# IOBoard.net
KiCad netlist of a schematic drawn in EAGLE
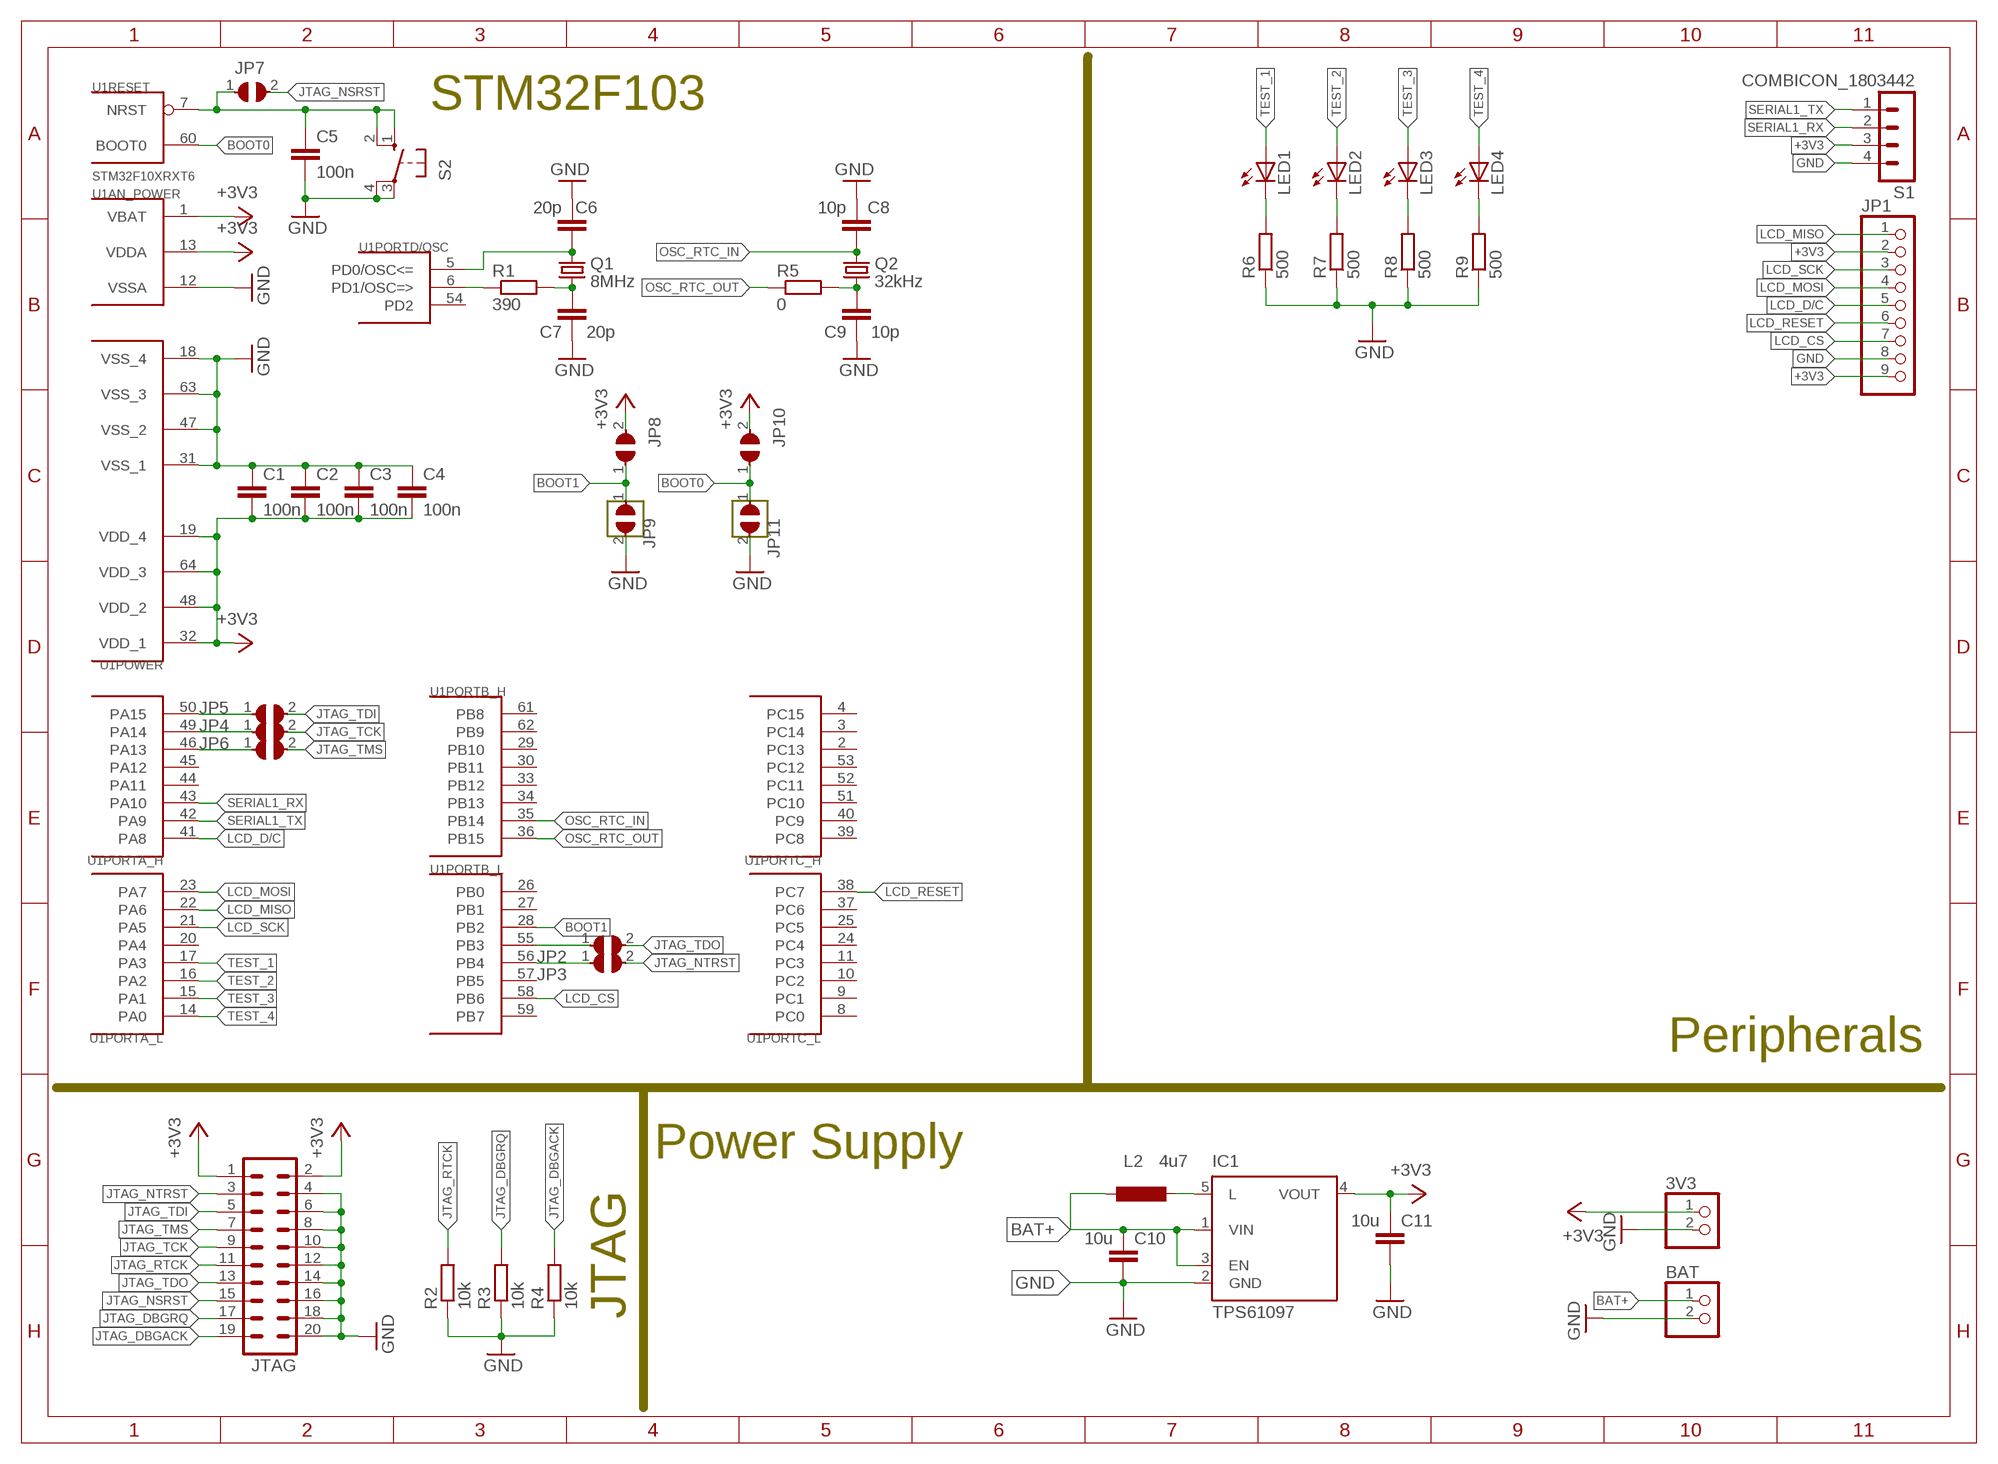
[diagram p0: schematic, sheet 1]

(export (version "E")
  (design (tool "Eeschema 10.0.6"))
  (components
    (comp (ref "3V3")
      (value "PINHD-1X2")
      (footprint "eagle-import:1X02")
      (libsource (lib "eagle-import") (part "PINHD-1X2"))
    )
    (comp (ref "BAT")
      (value "PINHD-1X2")
      (footprint "eagle-import:1X02")
      (libsource (lib "eagle-import") (part "PINHD-1X2"))
    )
    (comp (ref "C1")
      (value "100n")
      (footprint "eagle-import:C0805")
      (libsource (lib "eagle-import") (part "C-EUC0805"))
    )
    (comp (ref "C2")
      (value "100n")
      (footprint "eagle-import:C0805")
      (libsource (lib "eagle-import") (part "C-EUC0805"))
    )
    (comp (ref "C3")
      (value "100n")
      (footprint "eagle-import:C0805")
      (libsource (lib "eagle-import") (part "C-EUC0805"))
    )
    (comp (ref "C4")
      (value "100n")
      (footprint "eagle-import:C0805")
      (libsource (lib "eagle-import") (part "C-EUC0805"))
    )
    (comp (ref "C5")
      (value "100n")
      (footprint "eagle-import:C0805")
      (libsource (lib "eagle-import") (part "C-EUC0805"))
    )
    (comp (ref "C6")
      (value "20p")
      (footprint "eagle-import:C0805")
      (libsource (lib "eagle-import") (part "C-EUC0805"))
    )
    (comp (ref "C7")
      (value "20p")
      (footprint "eagle-import:C0805")
      (libsource (lib "eagle-import") (part "C-EUC0805"))
    )
    (comp (ref "C8")
      (value "10p")
      (footprint "eagle-import:C0805")
      (libsource (lib "eagle-import") (part "C-EUC0805"))
    )
    (comp (ref "C9")
      (value "10p")
      (footprint "eagle-import:C0805")
      (libsource (lib "eagle-import") (part "C-EUC0805"))
    )
    (comp (ref "C10")
      (value "10u")
      (footprint "eagle-import:C0805")
      (libsource (lib "eagle-import") (part "C-EUC0805"))
    )
    (comp (ref "C11")
      (value "10u")
      (footprint "eagle-import:C0805")
      (libsource (lib "eagle-import") (part "C-EUC0805"))
    )
    (comp (ref "IC1")
      (value "TPS61097")
      (footprint "eagle-import:SOT23-DBV")
      (libsource (lib "eagle-import") (part "TPS61097"))
    )
    (comp (ref "JP1")
      (value "PINHD-1X9")
      (footprint "eagle-import:1X09")
      (libsource (lib "eagle-import") (part "PINHD-1X9"))
    )
    (comp (ref "JP2")
      (value "JUMPER_SMALL")
      (footprint "eagle-import:JUMPER")
      (libsource (lib "eagle-import") (part "JUMPER_SMALL"))
    )
    (comp (ref "JP3")
      (value "JUMPER_SMALL")
      (footprint "eagle-import:JUMPER")
      (libsource (lib "eagle-import") (part "JUMPER_SMALL"))
    )
    (comp (ref "JP4")
      (value "JUMPER_SMALL")
      (footprint "eagle-import:JUMPER")
      (libsource (lib "eagle-import") (part "JUMPER_SMALL"))
    )
    (comp (ref "JP5")
      (value "JUMPER_SMALL")
      (footprint "eagle-import:JUMPER")
      (libsource (lib "eagle-import") (part "JUMPER_SMALL"))
    )
    (comp (ref "JP6")
      (value "JUMPER_SMALL")
      (footprint "eagle-import:JUMPER")
      (libsource (lib "eagle-import") (part "JUMPER_SMALL"))
    )
    (comp (ref "JP7")
      (value "JUMPER_SMALL")
      (footprint "eagle-import:JUMPER")
      (libsource (lib "eagle-import") (part "JUMPER_SMALL"))
    )
    (comp (ref "JP8")
      (value "JUMPER_SMALL")
      (footprint "eagle-import:JUMPER")
      (libsource (lib "eagle-import") (part "JUMPER_SMALL"))
    )
    (comp (ref "JP9")
      (value "JUMPER_SMALL")
      (footprint "eagle-import:JUMPER")
      (libsource (lib "eagle-import") (part "JUMPER_SMALL"))
    )
    (comp (ref "JP10")
      (value "JUMPER_SMALL")
      (footprint "eagle-import:JUMPER")
      (libsource (lib "eagle-import") (part "JUMPER_SMALL"))
    )
    (comp (ref "JP11")
      (value "JUMPER_SMALL")
      (footprint "eagle-import:JUMPER")
      (libsource (lib "eagle-import") (part "JUMPER_SMALL"))
    )
    (comp (ref "JTAG")
      (value "ML20")
      (footprint "eagle-import:ML20")
      (libsource (lib "eagle-import") (part "ML20"))
    )
    (comp (ref "L2")
      (value "4u7")
      (footprint "eagle-import:INDC6350X200N")
      (libsource (lib "eagle-import") (part "INDUCTOR_2520"))
    )
    (comp (ref "LED1")
      (value "LEDSML0603")
      (footprint "eagle-import:SML0603")
      (libsource (lib "eagle-import") (part "LEDSML0603"))
    )
    (comp (ref "LED2")
      (value "LEDSML0603")
      (footprint "eagle-import:SML0603")
      (libsource (lib "eagle-import") (part "LEDSML0603"))
    )
    (comp (ref "LED3")
      (value "LEDSML0603")
      (footprint "eagle-import:SML0603")
      (libsource (lib "eagle-import") (part "LEDSML0603"))
    )
    (comp (ref "LED4")
      (value "LEDSML0603")
      (footprint "eagle-import:SML0603")
      (libsource (lib "eagle-import") (part "LEDSML0603"))
    )
    (comp (ref "Q1")
      (value "8MHz")
      (footprint "eagle-import:CSM-7X-DU")
      (libsource (lib "eagle-import") (part "CSM-7X-DU"))
    )
    (comp (ref "Q2")
      (value "32kHz")
      (footprint "eagle-import:MC-306")
      (fields (field (name "MPN") "MC-306 60.0KHZ  100PPM ,12.5PF"))
      (libsource (lib "eagle-import") (part "MC-306"))
    )
    (comp (ref "R1")
      (value "390")
      (footprint "eagle-import:R0805")
      (libsource (lib "eagle-import") (part "R-EU_R0805"))
    )
    (comp (ref "R2")
      (value "10k")
      (footprint "eagle-import:R0805")
      (libsource (lib "eagle-import") (part "R-EU_R0805"))
    )
    (comp (ref "R3")
      (value "10k")
      (footprint "eagle-import:R0805")
      (libsource (lib "eagle-import") (part "R-EU_R0805"))
    )
    (comp (ref "R4")
      (value "10k")
      (footprint "eagle-import:R0805")
      (libsource (lib "eagle-import") (part "R-EU_R0805"))
    )
    (comp (ref "R5")
      (value "0")
      (footprint "eagle-import:R0805")
      (libsource (lib "eagle-import") (part "R-EU_R0805"))
    )
    (comp (ref "R6")
      (value "500")
      (footprint "eagle-import:R0805")
      (libsource (lib "eagle-import") (part "R-EU_R0805"))
    )
    (comp (ref "R7")
      (value "500")
      (footprint "eagle-import:R0805")
      (libsource (lib "eagle-import") (part "R-EU_R0805"))
    )
    (comp (ref "R8")
      (value "500")
      (footprint "eagle-import:R0805")
      (libsource (lib "eagle-import") (part "R-EU_R0805"))
    )
    (comp (ref "R9")
      (value "500")
      (footprint "eagle-import:R0805")
      (libsource (lib "eagle-import") (part "R-EU_R0805"))
    )
    (comp (ref "S1")
      (value "COMBICON_1803442")
      (footprint "eagle-import:COMBICON_1803442")
      (libsource (lib "eagle-import") (part "COMBICON_1803442"))
    )
    (comp (ref "S2")
      (value "10-XX")
      (footprint "eagle-import:B3F-10XX")
      (fields (field (name "MPN") "B3F-1000"))
      (libsource (lib "eagle-import") (part "10-XX"))
    )
    (comp (ref "U1")
      (value "STM32F10XRXT6")
      (footprint "eagle-import:TQFP64")
      (libsource (lib "eagle-import") (part "STM32F10XRXT6"))
    )
  )
  (nets
    (net (code "1") (name "+3V3") (class "Default")
      (node (ref "3V3") (pin "1") (pinfunction "1_1") (pintype "passive"))
      (node (ref "C1") (pin "2") (pinfunction "2_2") (pintype "passive"))
      (node (ref "C11") (pin "2") (pinfunction "2_2") (pintype "passive"))
      (node (ref "C2") (pin "2") (pinfunction "2_2") (pintype "passive"))
      (node (ref "C3") (pin "2") (pinfunction "2_2") (pintype "passive"))
      (node (ref "C4") (pin "2") (pinfunction "2_2") (pintype "passive"))
      (node (ref "IC1") (pin "4") (pinfunction "VOUT_4") (pintype "passive"))
      (node (ref "JP1") (pin "2") (pinfunction "2_2") (pintype "passive"))
      (node (ref "JP1") (pin "9") (pinfunction "9_9") (pintype "passive"))
      (node (ref "JP10") (pin "2") (pinfunction "2_2") (pintype "bidirectional"))
      (node (ref "JP8") (pin "2") (pinfunction "2_2") (pintype "bidirectional"))
      (node (ref "JTAG") (pin "1") (pinfunction "1_1") (pintype "passive"))
      (node (ref "JTAG") (pin "2") (pinfunction "2_2") (pintype "passive"))
      (node (ref "S1") (pin "3") (pinfunction "3_3") (pintype "passive"))
      (node (ref "U1") (pin "1") (pinfunction "VBAT_1") (pintype "power_in"))
      (node (ref "U1") (pin "13") (pinfunction "VDDA_13") (pintype "power_in"))
      (node (ref "U1") (pin "19") (pinfunction "VDD_4_19") (pintype "power_in"))
      (node (ref "U1") (pin "32") (pinfunction "VDD_1_32") (pintype "power_in"))
      (node (ref "U1") (pin "48") (pinfunction "VDD_2_48") (pintype "power_in"))
      (node (ref "U1") (pin "64") (pinfunction "VDD_3_64") (pintype "power_in"))
    )
    (net (code "2") (name "BAT+") (class "Default")
      (node (ref "BAT") (pin "1") (pinfunction "1_1") (pintype "passive"))
      (node (ref "C10") (pin "2") (pinfunction "2_2") (pintype "passive"))
      (node (ref "IC1") (pin "1") (pinfunction "VIN_1") (pintype "input"))
      (node (ref "IC1") (pin "3") (pinfunction "EN_3") (pintype "input"))
      (node (ref "L2") (pin "1") (pinfunction "1_1") (pintype "passive"))
    )
    (net (code "3") (name "BOOT0") (class "Default")
      (node (ref "JP10") (pin "1") (pinfunction "1_1") (pintype "bidirectional"))
      (node (ref "JP11") (pin "1") (pinfunction "1_1") (pintype "bidirectional"))
      (node (ref "U1") (pin "60") (pinfunction "BOOT0_60") (pintype "input"))
    )
    (net (code "4") (name "BOOT1") (class "Default")
      (node (ref "JP8") (pin "1") (pinfunction "1_1") (pintype "bidirectional"))
      (node (ref "JP9") (pin "1") (pinfunction "1_1") (pintype "bidirectional"))
      (node (ref "U1") (pin "28") (pinfunction "PB2_28") (pintype "bidirectional"))
    )
    (net (code "5") (name "GND") (class "Default")
      (node (ref "3V3") (pin "2") (pinfunction "2_2") (pintype "passive"))
      (node (ref "BAT") (pin "2") (pinfunction "2_2") (pintype "passive"))
      (node (ref "C1") (pin "1") (pinfunction "1_1") (pintype "passive"))
      (node (ref "C10") (pin "1") (pinfunction "1_1") (pintype "passive"))
      (node (ref "C11") (pin "1") (pinfunction "1_1") (pintype "passive"))
      (node (ref "C2") (pin "1") (pinfunction "1_1") (pintype "passive"))
      (node (ref "C3") (pin "1") (pinfunction "1_1") (pintype "passive"))
      (node (ref "C4") (pin "1") (pinfunction "1_1") (pintype "passive"))
      (node (ref "C5") (pin "2") (pinfunction "2_2") (pintype "passive"))
      (node (ref "C6") (pin "2") (pinfunction "2_2") (pintype "passive"))
      (node (ref "C7") (pin "1") (pinfunction "1_1") (pintype "passive"))
      (node (ref "C8") (pin "2") (pinfunction "2_2") (pintype "passive"))
      (node (ref "C9") (pin "1") (pinfunction "1_1") (pintype "passive"))
      (node (ref "IC1") (pin "2") (pinfunction "GND_2") (pintype "power_in"))
      (node (ref "JP1") (pin "8") (pinfunction "8_8") (pintype "passive"))
      (node (ref "JP11") (pin "2") (pinfunction "2_2") (pintype "bidirectional"))
      (node (ref "JP9") (pin "2") (pinfunction "2_2") (pintype "bidirectional"))
      (node (ref "JTAG") (pin "10") (pinfunction "10_10") (pintype "passive"))
      (node (ref "JTAG") (pin "12") (pinfunction "12_12") (pintype "passive"))
      (node (ref "JTAG") (pin "14") (pinfunction "14_14") (pintype "passive"))
      (node (ref "JTAG") (pin "16") (pinfunction "16_16") (pintype "passive"))
      (node (ref "JTAG") (pin "18") (pinfunction "18_18") (pintype "passive"))
      (node (ref "JTAG") (pin "20") (pinfunction "20_20") (pintype "passive"))
      (node (ref "JTAG") (pin "4") (pinfunction "4_4") (pintype "passive"))
      (node (ref "JTAG") (pin "6") (pinfunction "6_6") (pintype "passive"))
      (node (ref "JTAG") (pin "8") (pinfunction "8_8") (pintype "passive"))
      (node (ref "R2") (pin "1") (pinfunction "1_1") (pintype "passive"))
      (node (ref "R3") (pin "1") (pinfunction "1_1") (pintype "passive"))
      (node (ref "R4") (pin "1") (pinfunction "1_1") (pintype "passive"))
      (node (ref "R6") (pin "1") (pinfunction "1_1") (pintype "passive"))
      (node (ref "R7") (pin "1") (pinfunction "1_1") (pintype "passive"))
      (node (ref "R8") (pin "1") (pinfunction "1_1") (pintype "passive"))
      (node (ref "R9") (pin "1") (pinfunction "1_1") (pintype "passive"))
      (node (ref "S1") (pin "4") (pinfunction "4_4") (pintype "passive"))
      (node (ref "S2") (pin "3") (pinfunction "P_3") (pintype "passive"))
      (node (ref "S2") (pin "4") (pinfunction "P1_4") (pintype "passive"))
      (node (ref "U1") (pin "12") (pinfunction "VSSA_12") (pintype "power_in"))
      (node (ref "U1") (pin "18") (pinfunction "VSS_4_18") (pintype "power_in"))
      (node (ref "U1") (pin "31") (pinfunction "VSS_1_31") (pintype "power_in"))
      (node (ref "U1") (pin "47") (pinfunction "VSS_2_47") (pintype "power_in"))
      (node (ref "U1") (pin "63") (pinfunction "VSS_3_63") (pintype "power_in"))
    )
    (net (code "6") (name "JTAG_DBGACK") (class "Default")
      (node (ref "JTAG") (pin "19") (pinfunction "19_19") (pintype "passive"))
      (node (ref "R4") (pin "2") (pinfunction "2_2") (pintype "passive"))
    )
    (net (code "7") (name "JTAG_DBGRQ") (class "Default")
      (node (ref "JTAG") (pin "17") (pinfunction "17_17") (pintype "passive"))
      (node (ref "R3") (pin "2") (pinfunction "2_2") (pintype "passive"))
    )
    (net (code "8") (name "JTAG_NSRST") (class "Default")
      (node (ref "JP7") (pin "2") (pinfunction "2_2") (pintype "bidirectional"))
      (node (ref "JTAG") (pin "15") (pinfunction "15_15") (pintype "passive"))
    )
    (net (code "9") (name "JTAG_NTRST") (class "Default")
      (node (ref "JP3") (pin "2") (pinfunction "2_2") (pintype "bidirectional"))
      (node (ref "JTAG") (pin "3") (pinfunction "3_3") (pintype "passive"))
    )
    (net (code "10") (name "JTAG_RTCK") (class "Default")
      (node (ref "JTAG") (pin "11") (pinfunction "11_11") (pintype "passive"))
      (node (ref "R2") (pin "2") (pinfunction "2_2") (pintype "passive"))
    )
    (net (code "11") (name "JTAG_TCK") (class "Default")
      (node (ref "JP4") (pin "2") (pinfunction "2_2") (pintype "bidirectional"))
      (node (ref "JTAG") (pin "9") (pinfunction "9_9") (pintype "passive"))
    )
    (net (code "12") (name "JTAG_TDI") (class "Default")
      (node (ref "JP5") (pin "2") (pinfunction "2_2") (pintype "bidirectional"))
      (node (ref "JTAG") (pin "5") (pinfunction "5_5") (pintype "passive"))
    )
    (net (code "13") (name "JTAG_TDO") (class "Default")
      (node (ref "JP2") (pin "2") (pinfunction "2_2") (pintype "bidirectional"))
      (node (ref "JTAG") (pin "13") (pinfunction "13_13") (pintype "passive"))
    )
    (net (code "14") (name "JTAG_TMS") (class "Default")
      (node (ref "JP6") (pin "2") (pinfunction "2_2") (pintype "bidirectional"))
      (node (ref "JTAG") (pin "7") (pinfunction "7_7") (pintype "passive"))
    )
    (net (code "15") (name "LCD_CS") (class "Default")
      (node (ref "JP1") (pin "7") (pinfunction "7_7") (pintype "passive"))
      (node (ref "U1") (pin "58") (pinfunction "PB6_58") (pintype "bidirectional"))
    )
    (net (code "16") (name "LCD_D{slash}C") (class "Default")
      (node (ref "JP1") (pin "5") (pinfunction "5_5") (pintype "passive"))
      (node (ref "U1") (pin "41") (pinfunction "PA8_41") (pintype "bidirectional"))
    )
    (net (code "17") (name "LCD_MISO") (class "Default")
      (node (ref "JP1") (pin "1") (pinfunction "1_1") (pintype "passive"))
      (node (ref "U1") (pin "22") (pinfunction "PA6_22") (pintype "bidirectional"))
    )
    (net (code "18") (name "LCD_MOSI") (class "Default")
      (node (ref "JP1") (pin "4") (pinfunction "4_4") (pintype "passive"))
      (node (ref "U1") (pin "23") (pinfunction "PA7_23") (pintype "bidirectional"))
    )
    (net (code "19") (name "LCD_RESET") (class "Default")
      (node (ref "JP1") (pin "6") (pinfunction "6_6") (pintype "passive"))
      (node (ref "U1") (pin "38") (pinfunction "PC7_38") (pintype "bidirectional"))
    )
    (net (code "20") (name "LCD_SCK") (class "Default")
      (node (ref "JP1") (pin "3") (pinfunction "3_3") (pintype "passive"))
      (node (ref "U1") (pin "21") (pinfunction "PA5_21") (pintype "bidirectional"))
    )
    (net (code "21") (name "Net-(C7-Pad2)") (class "Default")
      (node (ref "C7") (pin "2") (pinfunction "2_2") (pintype "passive"))
      (node (ref "Q1") (pin "1") (pinfunction "1_1") (pintype "passive"))
      (node (ref "R1") (pin "2") (pinfunction "2_2") (pintype "passive"))
    )
    (net (code "22") (name "Net-(C9-Pad2)") (class "Default")
      (node (ref "C9") (pin "2") (pinfunction "2_2") (pintype "passive"))
      (node (ref "Q2") (pin "1") (pinfunction "1_1") (pintype "passive"))
      (node (ref "R5") (pin "2") (pinfunction "2_2") (pintype "passive"))
    )
    (net (code "23") (name "Net-(IC1-L)") (class "Default")
      (node (ref "IC1") (pin "5") (pinfunction "L_5") (pintype "input"))
      (node (ref "L2") (pin "2") (pinfunction "2_2") (pintype "passive"))
    )
    (net (code "24") (name "Net-(LED1-PadC)") (class "Default")
      (node (ref "LED1") (pin "C") (pinfunction "C_C") (pintype "passive"))
      (node (ref "R6") (pin "2") (pinfunction "2_2") (pintype "passive"))
    )
    (net (code "25") (name "Net-(LED2-PadC)") (class "Default")
      (node (ref "LED2") (pin "C") (pinfunction "C_C") (pintype "passive"))
      (node (ref "R7") (pin "2") (pinfunction "2_2") (pintype "passive"))
    )
    (net (code "26") (name "Net-(LED3-PadC)") (class "Default")
      (node (ref "LED3") (pin "C") (pinfunction "C_C") (pintype "passive"))
      (node (ref "R8") (pin "2") (pinfunction "2_2") (pintype "passive"))
    )
    (net (code "27") (name "Net-(LED4-PadC)") (class "Default")
      (node (ref "LED4") (pin "C") (pinfunction "C_C") (pintype "passive"))
      (node (ref "R9") (pin "2") (pinfunction "2_2") (pintype "passive"))
    )
    (net (code "28") (name "Net-(S2-S)") (class "Default")
      (node (ref "C5") (pin "1") (pinfunction "1_1") (pintype "passive"))
      (node (ref "JP7") (pin "1") (pinfunction "1_1") (pintype "bidirectional"))
      (node (ref "S2") (pin "1") (pinfunction "S_1") (pintype "passive"))
      (node (ref "S2") (pin "2") (pinfunction "S1_2") (pintype "passive"))
      (node (ref "U1") (pin "7") (pinfunction "NRST_7") (pintype "input"))
    )
    (net (code "29") (name "Net-(U1B-PA13)") (class "Default")
      (node (ref "JP6") (pin "1") (pinfunction "1_1") (pintype "bidirectional"))
      (node (ref "U1") (pin "46") (pinfunction "PA13_46") (pintype "bidirectional"))
    )
    (net (code "30") (name "Net-(U1B-PA14)") (class "Default")
      (node (ref "JP4") (pin "1") (pinfunction "1_1") (pintype "bidirectional"))
      (node (ref "U1") (pin "49") (pinfunction "PA14_49") (pintype "bidirectional"))
    )
    (net (code "31") (name "Net-(U1B-PA15)") (class "Default")
      (node (ref "JP5") (pin "1") (pinfunction "1_1") (pintype "bidirectional"))
      (node (ref "U1") (pin "50") (pinfunction "PA15_50") (pintype "bidirectional"))
    )
    (net (code "32") (name "Net-(U1E-PB3)") (class "Default")
      (node (ref "JP2") (pin "1") (pinfunction "1_1") (pintype "bidirectional"))
      (node (ref "U1") (pin "55") (pinfunction "PB3_55") (pintype "bidirectional"))
    )
    (net (code "33") (name "Net-(U1E-PB4)") (class "Default")
      (node (ref "JP3") (pin "1") (pinfunction "1_1") (pintype "bidirectional"))
      (node (ref "U1") (pin "56") (pinfunction "PB4_56") (pintype "bidirectional"))
    )
    (net (code "34") (name "Net-(U1H-PD0{slash}OSC<=)") (class "Default")
      (node (ref "C6") (pin "1") (pinfunction "1_1") (pintype "passive"))
      (node (ref "Q1") (pin "2") (pinfunction "2_2") (pintype "passive"))
      (node (ref "U1") (pin "5") (pinfunction "PD0/OSC<=_5") (pintype "bidirectional"))
    )
    (net (code "35") (name "Net-(U1H-PD1{slash}OSC=>)") (class "Default")
      (node (ref "R1") (pin "1") (pinfunction "1_1") (pintype "passive"))
      (node (ref "U1") (pin "6") (pinfunction "PD1/OSC=>_6") (pintype "bidirectional"))
    )
    (net (code "36") (name "OSC_RTC_IN") (class "Default")
      (node (ref "C8") (pin "1") (pinfunction "1_1") (pintype "passive"))
      (node (ref "Q2") (pin "4") (pinfunction "2_4") (pintype "passive"))
      (node (ref "U1") (pin "35") (pinfunction "PB14_35") (pintype "bidirectional"))
    )
    (net (code "37") (name "OSC_RTC_OUT") (class "Default")
      (node (ref "R5") (pin "1") (pinfunction "1_1") (pintype "passive"))
      (node (ref "U1") (pin "36") (pinfunction "PB15_36") (pintype "bidirectional"))
    )
    (net (code "38") (name "SERIAL1_RX") (class "Default")
      (node (ref "S1") (pin "2") (pinfunction "2_2") (pintype "passive"))
      (node (ref "U1") (pin "43") (pinfunction "PA10_43") (pintype "bidirectional"))
    )
    (net (code "39") (name "SERIAL1_TX") (class "Default")
      (node (ref "S1") (pin "1") (pinfunction "1_1") (pintype "passive"))
      (node (ref "U1") (pin "42") (pinfunction "PA9_42") (pintype "bidirectional"))
    )
    (net (code "40") (name "TEST_1") (class "Default")
      (node (ref "LED1") (pin "A") (pinfunction "A_A") (pintype "passive"))
      (node (ref "U1") (pin "17") (pinfunction "PA3_17") (pintype "bidirectional"))
    )
    (net (code "41") (name "TEST_2") (class "Default")
      (node (ref "LED2") (pin "A") (pinfunction "A_A") (pintype "passive"))
      (node (ref "U1") (pin "16") (pinfunction "PA2_16") (pintype "bidirectional"))
    )
    (net (code "42") (name "TEST_3") (class "Default")
      (node (ref "LED3") (pin "A") (pinfunction "A_A") (pintype "passive"))
      (node (ref "U1") (pin "15") (pinfunction "PA1_15") (pintype "bidirectional"))
    )
    (net (code "43") (name "TEST_4") (class "Default")
      (node (ref "LED4") (pin "A") (pinfunction "A_A") (pintype "passive"))
      (node (ref "U1") (pin "14") (pinfunction "PA0_14") (pintype "bidirectional"))
    )
    (net (code "44") (name "unconnected-(U1B-PA11-Pad44)") (class "Default")
      (node (ref "U1") (pin "44") (pinfunction "PA11_44") (pintype "bidirectional"))
    )
    (net (code "45") (name "unconnected-(U1B-PA12-Pad45)") (class "Default")
      (node (ref "U1") (pin "45") (pinfunction "PA12_45") (pintype "bidirectional"))
    )
    (net (code "46") (name "unconnected-(U1C-PA4-Pad20)") (class "Default")
      (node (ref "U1") (pin "20") (pinfunction "PA4_20") (pintype "bidirectional"))
    )
    (net (code "47") (name "unconnected-(U1D-PB8-Pad61)") (class "Default")
      (node (ref "U1") (pin "61") (pinfunction "PB8_61") (pintype "bidirectional"))
    )
    (net (code "48") (name "unconnected-(U1D-PB9-Pad62)") (class "Default")
      (node (ref "U1") (pin "62") (pinfunction "PB9_62") (pintype "bidirectional"))
    )
    (net (code "49") (name "unconnected-(U1D-PB10-Pad29)") (class "Default")
      (node (ref "U1") (pin "29") (pinfunction "PB10_29") (pintype "bidirectional"))
    )
    (net (code "50") (name "unconnected-(U1D-PB11-Pad30)") (class "Default")
      (node (ref "U1") (pin "30") (pinfunction "PB11_30") (pintype "bidirectional"))
    )
    (net (code "51") (name "unconnected-(U1D-PB12-Pad33)") (class "Default")
      (node (ref "U1") (pin "33") (pinfunction "PB12_33") (pintype "bidirectional"))
    )
    (net (code "52") (name "unconnected-(U1D-PB13-Pad34)") (class "Default")
      (node (ref "U1") (pin "34") (pinfunction "PB13_34") (pintype "bidirectional"))
    )
    (net (code "53") (name "unconnected-(U1E-PB0-Pad26)") (class "Default")
      (node (ref "U1") (pin "26") (pinfunction "PB0_26") (pintype "bidirectional"))
    )
    (net (code "54") (name "unconnected-(U1E-PB1-Pad27)") (class "Default")
      (node (ref "U1") (pin "27") (pinfunction "PB1_27") (pintype "bidirectional"))
    )
    (net (code "55") (name "unconnected-(U1E-PB5-Pad57)") (class "Default")
      (node (ref "U1") (pin "57") (pinfunction "PB5_57") (pintype "bidirectional"))
    )
    (net (code "56") (name "unconnected-(U1E-PB7-Pad59)") (class "Default")
      (node (ref "U1") (pin "59") (pinfunction "PB7_59") (pintype "bidirectional"))
    )
    (net (code "57") (name "unconnected-(U1F-PC8-Pad39)") (class "Default")
      (node (ref "U1") (pin "39") (pinfunction "PC8_39") (pintype "bidirectional"))
    )
    (net (code "58") (name "unconnected-(U1F-PC9-Pad40)") (class "Default")
      (node (ref "U1") (pin "40") (pinfunction "PC9_40") (pintype "bidirectional"))
    )
    (net (code "59") (name "unconnected-(U1F-PC10-Pad51)") (class "Default")
      (node (ref "U1") (pin "51") (pinfunction "PC10_51") (pintype "bidirectional"))
    )
    (net (code "60") (name "unconnected-(U1F-PC11-Pad52)") (class "Default")
      (node (ref "U1") (pin "52") (pinfunction "PC11_52") (pintype "bidirectional"))
    )
    (net (code "61") (name "unconnected-(U1F-PC12-Pad53)") (class "Default")
      (node (ref "U1") (pin "53") (pinfunction "PC12_53") (pintype "bidirectional"))
    )
    (net (code "62") (name "unconnected-(U1F-PC13-Pad2)") (class "Default")
      (node (ref "U1") (pin "2") (pinfunction "PC13_2") (pintype "bidirectional"))
    )
    (net (code "63") (name "unconnected-(U1F-PC14-Pad3)") (class "Default")
      (node (ref "U1") (pin "3") (pinfunction "PC14_3") (pintype "bidirectional"))
    )
    (net (code "64") (name "unconnected-(U1F-PC15-Pad4)") (class "Default")
      (node (ref "U1") (pin "4") (pinfunction "PC15_4") (pintype "bidirectional"))
    )
    (net (code "65") (name "unconnected-(U1G-PC0-Pad8)") (class "Default")
      (node (ref "U1") (pin "8") (pinfunction "PC0_8") (pintype "bidirectional"))
    )
    (net (code "66") (name "unconnected-(U1G-PC1-Pad9)") (class "Default")
      (node (ref "U1") (pin "9") (pinfunction "PC1_9") (pintype "bidirectional"))
    )
    (net (code "67") (name "unconnected-(U1G-PC2-Pad10)") (class "Default")
      (node (ref "U1") (pin "10") (pinfunction "PC2_10") (pintype "bidirectional"))
    )
    (net (code "68") (name "unconnected-(U1G-PC3-Pad11)") (class "Default")
      (node (ref "U1") (pin "11") (pinfunction "PC3_11") (pintype "bidirectional"))
    )
    (net (code "69") (name "unconnected-(U1G-PC4-Pad24)") (class "Default")
      (node (ref "U1") (pin "24") (pinfunction "PC4_24") (pintype "bidirectional"))
    )
    (net (code "70") (name "unconnected-(U1G-PC5-Pad25)") (class "Default")
      (node (ref "U1") (pin "25") (pinfunction "PC5_25") (pintype "bidirectional"))
    )
    (net (code "71") (name "unconnected-(U1G-PC6-Pad37)") (class "Default")
      (node (ref "U1") (pin "37") (pinfunction "PC6_37") (pintype "bidirectional"))
    )
    (net (code "72") (name "unconnected-(U1H-PD2-Pad54)") (class "Default")
      (node (ref "U1") (pin "54") (pinfunction "PD2_54") (pintype "bidirectional"))
    )
  )
)
